# gamifyPCB.net
KiCad netlist of a schematic drawn in EAGLE
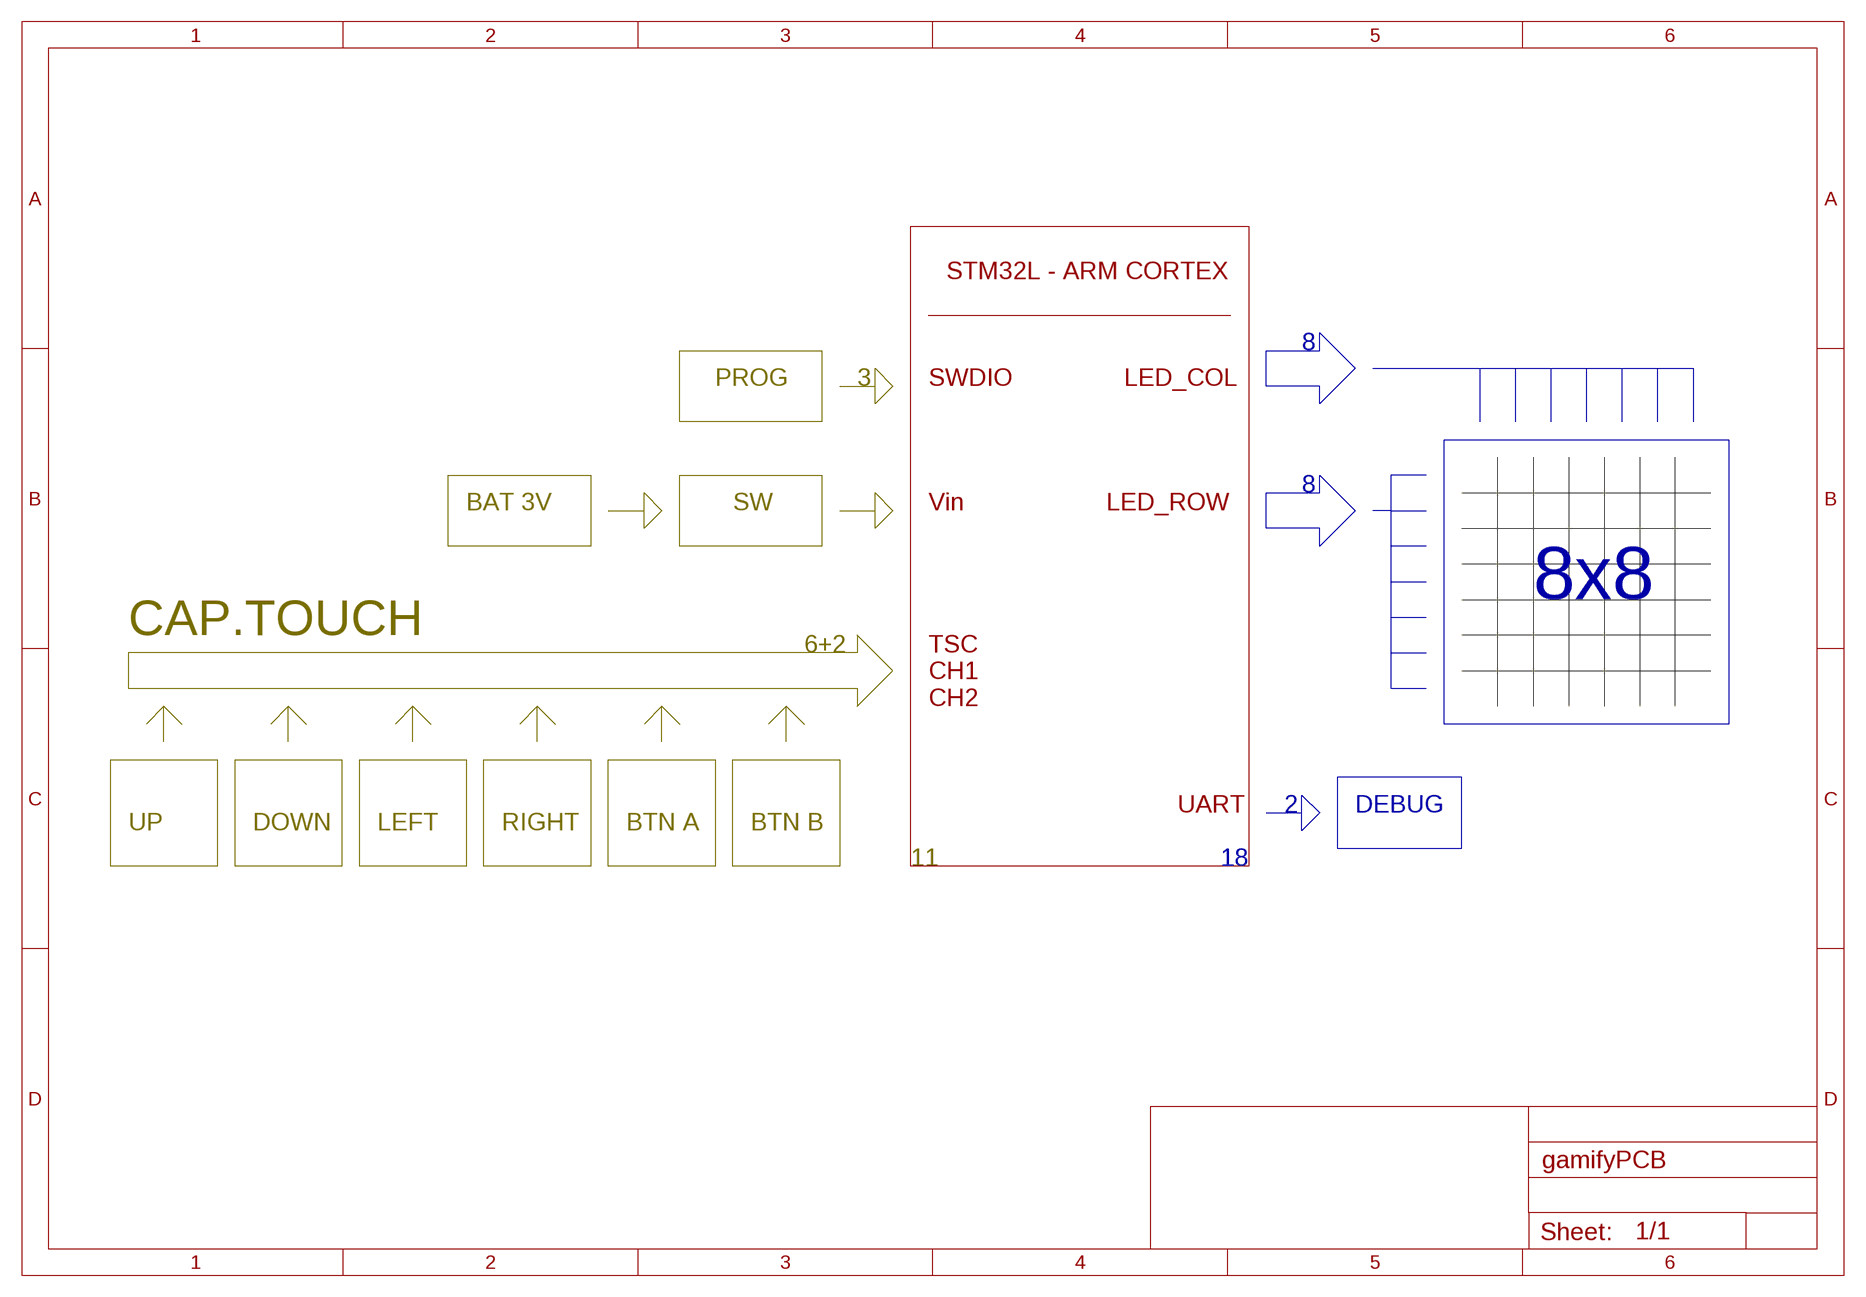
[diagram p0: schematic, sheet 1, part 1 of 2]
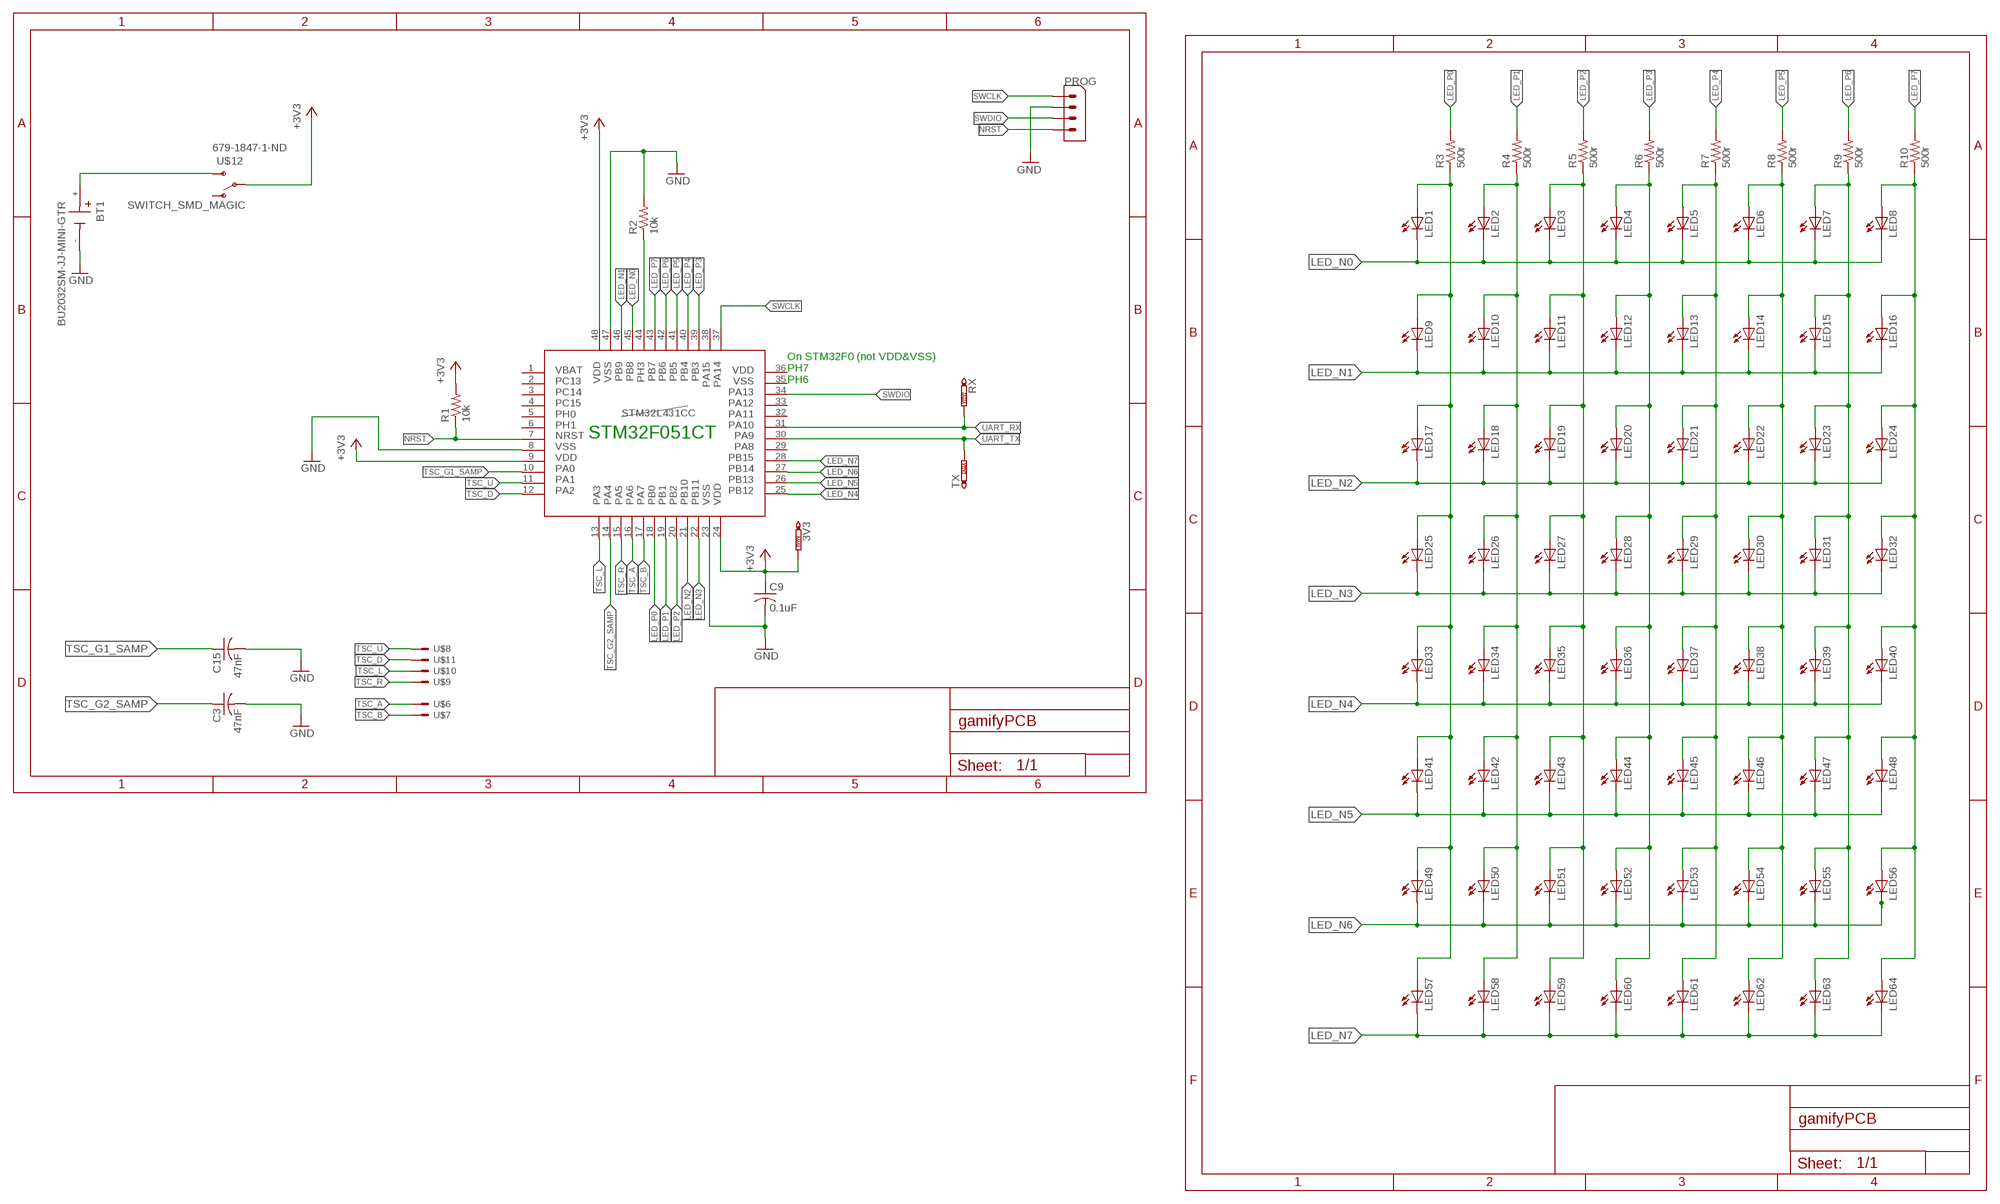
[diagram p1: schematic, sheet 1, part 2 of 2]

(export (version "E")
  (design (tool "Eeschema 10.0.6"))
  (components
    (comp (ref "3V3")
      (value "PTR1B1,27")
      (footprint "eagle-import:B1,27")
      (libsource (lib "eagle-import") (part "PTR1B1,27"))
    )
    (comp (ref "BT1")
      (value "BU2032SM-JJ-MINI-GTR")
      (footprint "eagle-import:BAT_BU2032SM-JJ-MINI-GTR")
      (fields (field (name "MF") "MPD _Memory"))
      (libsource (lib "eagle-import") (part "BU2032SM-JJ-MINI-GTR"))
    )
    (comp (ref "C3")
      (value "47nF")
      (footprint "eagle-import:C0603")
      (libsource (lib "eagle-import") (part "C-USC0603"))
    )
    (comp (ref "C9")
      (value "0.1uF")
      (footprint "eagle-import:C0603")
      (libsource (lib "eagle-import") (part "C-USC0603"))
    )
    (comp (ref "C15")
      (value "47nF")
      (footprint "eagle-import:C0603")
      (libsource (lib "eagle-import") (part "C-USC0603"))
    )
    (comp (ref "LED1")
      (value "LEDCHIP-LED0603")
      (footprint "eagle-import:CHIP-LED0603")
      (libsource (lib "eagle-import") (part "LEDCHIP-LED0603"))
    )
    (comp (ref "LED2")
      (value "LEDCHIP-LED0603")
      (footprint "eagle-import:CHIP-LED0603")
      (libsource (lib "eagle-import") (part "LEDCHIP-LED0603"))
    )
    (comp (ref "LED3")
      (value "LEDCHIP-LED0603")
      (footprint "eagle-import:CHIP-LED0603")
      (libsource (lib "eagle-import") (part "LEDCHIP-LED0603"))
    )
    (comp (ref "LED4")
      (value "LEDCHIP-LED0603")
      (footprint "eagle-import:CHIP-LED0603")
      (libsource (lib "eagle-import") (part "LEDCHIP-LED0603"))
    )
    (comp (ref "LED5")
      (value "LEDCHIP-LED0603")
      (footprint "eagle-import:CHIP-LED0603")
      (libsource (lib "eagle-import") (part "LEDCHIP-LED0603"))
    )
    (comp (ref "LED6")
      (value "LEDCHIP-LED0603")
      (footprint "eagle-import:CHIP-LED0603")
      (libsource (lib "eagle-import") (part "LEDCHIP-LED0603"))
    )
    (comp (ref "LED7")
      (value "LEDCHIP-LED0603")
      (footprint "eagle-import:CHIP-LED0603")
      (libsource (lib "eagle-import") (part "LEDCHIP-LED0603"))
    )
    (comp (ref "LED8")
      (value "LEDCHIP-LED0603")
      (footprint "eagle-import:CHIP-LED0603")
      (libsource (lib "eagle-import") (part "LEDCHIP-LED0603"))
    )
    (comp (ref "LED9")
      (value "LEDCHIP-LED0603")
      (footprint "eagle-import:CHIP-LED0603")
      (libsource (lib "eagle-import") (part "LEDCHIP-LED0603"))
    )
    (comp (ref "LED10")
      (value "LEDCHIP-LED0603")
      (footprint "eagle-import:CHIP-LED0603")
      (libsource (lib "eagle-import") (part "LEDCHIP-LED0603"))
    )
    (comp (ref "LED11")
      (value "LEDCHIP-LED0603")
      (footprint "eagle-import:CHIP-LED0603")
      (libsource (lib "eagle-import") (part "LEDCHIP-LED0603"))
    )
    (comp (ref "LED12")
      (value "LEDCHIP-LED0603")
      (footprint "eagle-import:CHIP-LED0603")
      (libsource (lib "eagle-import") (part "LEDCHIP-LED0603"))
    )
    (comp (ref "LED13")
      (value "LEDCHIP-LED0603")
      (footprint "eagle-import:CHIP-LED0603")
      (libsource (lib "eagle-import") (part "LEDCHIP-LED0603"))
    )
    (comp (ref "LED14")
      (value "LEDCHIP-LED0603")
      (footprint "eagle-import:CHIP-LED0603")
      (libsource (lib "eagle-import") (part "LEDCHIP-LED0603"))
    )
    (comp (ref "LED15")
      (value "LEDCHIP-LED0603")
      (footprint "eagle-import:CHIP-LED0603")
      (libsource (lib "eagle-import") (part "LEDCHIP-LED0603"))
    )
    (comp (ref "LED16")
      (value "LEDCHIP-LED0603")
      (footprint "eagle-import:CHIP-LED0603")
      (libsource (lib "eagle-import") (part "LEDCHIP-LED0603"))
    )
    (comp (ref "LED17")
      (value "LEDCHIP-LED0603")
      (footprint "eagle-import:CHIP-LED0603")
      (libsource (lib "eagle-import") (part "LEDCHIP-LED0603"))
    )
    (comp (ref "LED18")
      (value "LEDCHIP-LED0603")
      (footprint "eagle-import:CHIP-LED0603")
      (libsource (lib "eagle-import") (part "LEDCHIP-LED0603"))
    )
    (comp (ref "LED19")
      (value "LEDCHIP-LED0603")
      (footprint "eagle-import:CHIP-LED0603")
      (libsource (lib "eagle-import") (part "LEDCHIP-LED0603"))
    )
    (comp (ref "LED20")
      (value "LEDCHIP-LED0603")
      (footprint "eagle-import:CHIP-LED0603")
      (libsource (lib "eagle-import") (part "LEDCHIP-LED0603"))
    )
    (comp (ref "LED21")
      (value "LEDCHIP-LED0603")
      (footprint "eagle-import:CHIP-LED0603")
      (libsource (lib "eagle-import") (part "LEDCHIP-LED0603"))
    )
    (comp (ref "LED22")
      (value "LEDCHIP-LED0603")
      (footprint "eagle-import:CHIP-LED0603")
      (libsource (lib "eagle-import") (part "LEDCHIP-LED0603"))
    )
    (comp (ref "LED23")
      (value "LEDCHIP-LED0603")
      (footprint "eagle-import:CHIP-LED0603")
      (libsource (lib "eagle-import") (part "LEDCHIP-LED0603"))
    )
    (comp (ref "LED24")
      (value "LEDCHIP-LED0603")
      (footprint "eagle-import:CHIP-LED0603")
      (libsource (lib "eagle-import") (part "LEDCHIP-LED0603"))
    )
    (comp (ref "LED25")
      (value "LEDCHIP-LED0603")
      (footprint "eagle-import:CHIP-LED0603")
      (libsource (lib "eagle-import") (part "LEDCHIP-LED0603"))
    )
    (comp (ref "LED26")
      (value "LEDCHIP-LED0603")
      (footprint "eagle-import:CHIP-LED0603")
      (libsource (lib "eagle-import") (part "LEDCHIP-LED0603"))
    )
    (comp (ref "LED27")
      (value "LEDCHIP-LED0603")
      (footprint "eagle-import:CHIP-LED0603")
      (libsource (lib "eagle-import") (part "LEDCHIP-LED0603"))
    )
    (comp (ref "LED28")
      (value "LEDCHIP-LED0603")
      (footprint "eagle-import:CHIP-LED0603")
      (libsource (lib "eagle-import") (part "LEDCHIP-LED0603"))
    )
    (comp (ref "LED29")
      (value "LEDCHIP-LED0603")
      (footprint "eagle-import:CHIP-LED0603")
      (libsource (lib "eagle-import") (part "LEDCHIP-LED0603"))
    )
    (comp (ref "LED30")
      (value "LEDCHIP-LED0603")
      (footprint "eagle-import:CHIP-LED0603")
      (libsource (lib "eagle-import") (part "LEDCHIP-LED0603"))
    )
    (comp (ref "LED31")
      (value "LEDCHIP-LED0603")
      (footprint "eagle-import:CHIP-LED0603")
      (libsource (lib "eagle-import") (part "LEDCHIP-LED0603"))
    )
    (comp (ref "LED32")
      (value "LEDCHIP-LED0603")
      (footprint "eagle-import:CHIP-LED0603")
      (libsource (lib "eagle-import") (part "LEDCHIP-LED0603"))
    )
    (comp (ref "LED33")
      (value "LEDCHIP-LED0603")
      (footprint "eagle-import:CHIP-LED0603")
      (libsource (lib "eagle-import") (part "LEDCHIP-LED0603"))
    )
    (comp (ref "LED34")
      (value "LEDCHIP-LED0603")
      (footprint "eagle-import:CHIP-LED0603")
      (libsource (lib "eagle-import") (part "LEDCHIP-LED0603"))
    )
    (comp (ref "LED35")
      (value "LEDCHIP-LED0603")
      (footprint "eagle-import:CHIP-LED0603")
      (libsource (lib "eagle-import") (part "LEDCHIP-LED0603"))
    )
    (comp (ref "LED36")
      (value "LEDCHIP-LED0603")
      (footprint "eagle-import:CHIP-LED0603")
      (libsource (lib "eagle-import") (part "LEDCHIP-LED0603"))
    )
    (comp (ref "LED37")
      (value "LEDCHIP-LED0603")
      (footprint "eagle-import:CHIP-LED0603")
      (libsource (lib "eagle-import") (part "LEDCHIP-LED0603"))
    )
    (comp (ref "LED38")
      (value "LEDCHIP-LED0603")
      (footprint "eagle-import:CHIP-LED0603")
      (libsource (lib "eagle-import") (part "LEDCHIP-LED0603"))
    )
    (comp (ref "LED39")
      (value "LEDCHIP-LED0603")
      (footprint "eagle-import:CHIP-LED0603")
      (libsource (lib "eagle-import") (part "LEDCHIP-LED0603"))
    )
    (comp (ref "LED40")
      (value "LEDCHIP-LED0603")
      (footprint "eagle-import:CHIP-LED0603")
      (libsource (lib "eagle-import") (part "LEDCHIP-LED0603"))
    )
    (comp (ref "LED41")
      (value "LEDCHIP-LED0603")
      (footprint "eagle-import:CHIP-LED0603")
      (libsource (lib "eagle-import") (part "LEDCHIP-LED0603"))
    )
    (comp (ref "LED42")
      (value "LEDCHIP-LED0603")
      (footprint "eagle-import:CHIP-LED0603")
      (libsource (lib "eagle-import") (part "LEDCHIP-LED0603"))
    )
    (comp (ref "LED43")
      (value "LEDCHIP-LED0603")
      (footprint "eagle-import:CHIP-LED0603")
      (libsource (lib "eagle-import") (part "LEDCHIP-LED0603"))
    )
    (comp (ref "LED44")
      (value "LEDCHIP-LED0603")
      (footprint "eagle-import:CHIP-LED0603")
      (libsource (lib "eagle-import") (part "LEDCHIP-LED0603"))
    )
    (comp (ref "LED45")
      (value "LEDCHIP-LED0603")
      (footprint "eagle-import:CHIP-LED0603")
      (libsource (lib "eagle-import") (part "LEDCHIP-LED0603"))
    )
    (comp (ref "LED46")
      (value "LEDCHIP-LED0603")
      (footprint "eagle-import:CHIP-LED0603")
      (libsource (lib "eagle-import") (part "LEDCHIP-LED0603"))
    )
    (comp (ref "LED47")
      (value "LEDCHIP-LED0603")
      (footprint "eagle-import:CHIP-LED0603")
      (libsource (lib "eagle-import") (part "LEDCHIP-LED0603"))
    )
    (comp (ref "LED48")
      (value "LEDCHIP-LED0603")
      (footprint "eagle-import:CHIP-LED0603")
      (libsource (lib "eagle-import") (part "LEDCHIP-LED0603"))
    )
    (comp (ref "LED49")
      (value "LEDCHIP-LED0603")
      (footprint "eagle-import:CHIP-LED0603")
      (libsource (lib "eagle-import") (part "LEDCHIP-LED0603"))
    )
    (comp (ref "LED50")
      (value "LEDCHIP-LED0603")
      (footprint "eagle-import:CHIP-LED0603")
      (libsource (lib "eagle-import") (part "LEDCHIP-LED0603"))
    )
    (comp (ref "LED51")
      (value "LEDCHIP-LED0603")
      (footprint "eagle-import:CHIP-LED0603")
      (libsource (lib "eagle-import") (part "LEDCHIP-LED0603"))
    )
    (comp (ref "LED52")
      (value "LEDCHIP-LED0603")
      (footprint "eagle-import:CHIP-LED0603")
      (libsource (lib "eagle-import") (part "LEDCHIP-LED0603"))
    )
    (comp (ref "LED53")
      (value "LEDCHIP-LED0603")
      (footprint "eagle-import:CHIP-LED0603")
      (libsource (lib "eagle-import") (part "LEDCHIP-LED0603"))
    )
    (comp (ref "LED54")
      (value "LEDCHIP-LED0603")
      (footprint "eagle-import:CHIP-LED0603")
      (libsource (lib "eagle-import") (part "LEDCHIP-LED0603"))
    )
    (comp (ref "LED55")
      (value "LEDCHIP-LED0603")
      (footprint "eagle-import:CHIP-LED0603")
      (libsource (lib "eagle-import") (part "LEDCHIP-LED0603"))
    )
    (comp (ref "LED56")
      (value "LEDCHIP-LED0603")
      (footprint "eagle-import:CHIP-LED0603")
      (libsource (lib "eagle-import") (part "LEDCHIP-LED0603"))
    )
    (comp (ref "LED57")
      (value "LEDCHIP-LED0603")
      (footprint "eagle-import:CHIP-LED0603")
      (libsource (lib "eagle-import") (part "LEDCHIP-LED0603"))
    )
    (comp (ref "LED58")
      (value "LEDCHIP-LED0603")
      (footprint "eagle-import:CHIP-LED0603")
      (libsource (lib "eagle-import") (part "LEDCHIP-LED0603"))
    )
    (comp (ref "LED59")
      (value "LEDCHIP-LED0603")
      (footprint "eagle-import:CHIP-LED0603")
      (libsource (lib "eagle-import") (part "LEDCHIP-LED0603"))
    )
    (comp (ref "LED60")
      (value "LEDCHIP-LED0603")
      (footprint "eagle-import:CHIP-LED0603")
      (libsource (lib "eagle-import") (part "LEDCHIP-LED0603"))
    )
    (comp (ref "LED61")
      (value "LEDCHIP-LED0603")
      (footprint "eagle-import:CHIP-LED0603")
      (libsource (lib "eagle-import") (part "LEDCHIP-LED0603"))
    )
    (comp (ref "LED62")
      (value "LEDCHIP-LED0603")
      (footprint "eagle-import:CHIP-LED0603")
      (libsource (lib "eagle-import") (part "LEDCHIP-LED0603"))
    )
    (comp (ref "LED63")
      (value "LEDCHIP-LED0603")
      (footprint "eagle-import:CHIP-LED0603")
      (libsource (lib "eagle-import") (part "LEDCHIP-LED0603"))
    )
    (comp (ref "LED64")
      (value "LEDCHIP-LED0603")
      (footprint "eagle-import:CHIP-LED0603")
      (libsource (lib "eagle-import") (part "LEDCHIP-LED0603"))
    )
    (comp (ref "PROG")
      (value "4-PIN-1.25MM")
      (footprint "eagle-import:4-PIN-1.25MM")
      (libsource (lib "eagle-import") (part "4-PIN-1.25MM"))
    )
    (comp (ref "R1")
      (value "10k")
      (footprint "eagle-import:R0603")
      (libsource (lib "eagle-import") (part "R-US_R0603"))
    )
    (comp (ref "R2")
      (value "10k")
      (footprint "eagle-import:R0603")
      (libsource (lib "eagle-import") (part "R-US_R0603"))
    )
    (comp (ref "R3")
      (value "500r")
      (footprint "eagle-import:R0603")
      (libsource (lib "eagle-import") (part "R-US_R0603"))
    )
    (comp (ref "R4")
      (value "500r")
      (footprint "eagle-import:R0603")
      (libsource (lib "eagle-import") (part "R-US_R0603"))
    )
    (comp (ref "R5")
      (value "500r")
      (footprint "eagle-import:R0603")
      (libsource (lib "eagle-import") (part "R-US_R0603"))
    )
    (comp (ref "R6")
      (value "500r")
      (footprint "eagle-import:R0603")
      (libsource (lib "eagle-import") (part "R-US_R0603"))
    )
    (comp (ref "R7")
      (value "500r")
      (footprint "eagle-import:R0603")
      (libsource (lib "eagle-import") (part "R-US_R0603"))
    )
    (comp (ref "R8")
      (value "500r")
      (footprint "eagle-import:R0603")
      (libsource (lib "eagle-import") (part "R-US_R0603"))
    )
    (comp (ref "R9")
      (value "500r")
      (footprint "eagle-import:R0603")
      (libsource (lib "eagle-import") (part "R-US_R0603"))
    )
    (comp (ref "R10")
      (value "500r")
      (footprint "eagle-import:R0603")
      (libsource (lib "eagle-import") (part "R-US_R0603"))
    )
    (comp (ref "RX")
      (value "PTR1B1,27")
      (footprint "eagle-import:B1,27")
      (libsource (lib "eagle-import") (part "PTR1B1,27"))
    )
    (comp (ref "TX")
      (value "PTR1B1,27")
      (footprint "eagle-import:B1,27")
      (libsource (lib "eagle-import") (part "PTR1B1,27"))
    )
    (comp (ref "U$2")
      (value "STM32L431CC")
      (footprint "eagle-import:QFP50P900X900X160-48")
      (libsource (lib "eagle-import") (part "STM32L431CC"))
    )
    (comp (ref "U$6")
      (value "CAP_BUTTON")
      (footprint "eagle-import:CAPBUTTON")
      (libsource (lib "eagle-import") (part "CAP_BUTTON"))
    )
    (comp (ref "U$7")
      (value "CAP_BUTTON")
      (footprint "eagle-import:CAPBUTTON")
      (libsource (lib "eagle-import") (part "CAP_BUTTON"))
    )
    (comp (ref "U$8")
      (value "CAP_DPAD")
      (footprint "eagle-import:DPAD")
      (libsource (lib "eagle-import") (part "CAP_DPAD"))
    )
    (comp (ref "U$9")
      (value "CAP_DPAD")
      (footprint "eagle-import:DPAD")
      (libsource (lib "eagle-import") (part "CAP_DPAD"))
    )
    (comp (ref "U$10")
      (value "CAP_DPAD")
      (footprint "eagle-import:DPAD")
      (libsource (lib "eagle-import") (part "CAP_DPAD"))
    )
    (comp (ref "U$11")
      (value "CAP_DPAD")
      (footprint "eagle-import:DPAD")
      (libsource (lib "eagle-import") (part "CAP_DPAD"))
    )
    (comp (ref "U$12")
      (value "SWITCH_SMD_MAGIC")
      (footprint "eagle-import:SWITCH_SMD_SUNKEN")
      (libsource (lib "eagle-import") (part "SWITCH_SMD_MAGIC"))
    )
  )
  (nets
    (net (code "1") (name "+3V3") (class "Default")
      (node (ref "3V3") (pin "TP") (pinfunction "TP_TP") (pintype "input"))
      (node (ref "C9") (pin "1") (pinfunction "1_1") (pintype "passive"))
      (node (ref "R1") (pin "2") (pinfunction "2_2") (pintype "passive"))
      (node (ref "U$12") (pin "2") (pinfunction "P_2") (pintype "passive"))
      (node (ref "U$2") (pin "24") (pinfunction "P$24_24") (pintype "bidirectional"))
      (node (ref "U$2") (pin "48") (pinfunction "P$48_48") (pintype "bidirectional"))
      (node (ref "U$2") (pin "9") (pinfunction "P$9_9") (pintype "bidirectional"))
    )
    (net (code "2") (name "GND") (class "Default")
      (node (ref "BT1") (pin "-") (pinfunction "-_-") (pintype "passive"))
      (node (ref "C15") (pin "2") (pinfunction "2_2") (pintype "passive"))
      (node (ref "C3") (pin "2") (pinfunction "2_2") (pintype "passive"))
      (node (ref "C9") (pin "2") (pinfunction "2_2") (pintype "passive"))
      (node (ref "PROG") (pin "P$3") (pinfunction "2_P$3") (pintype "bidirectional"))
      (node (ref "R2") (pin "2") (pinfunction "2_2") (pintype "passive"))
      (node (ref "U$2") (pin "23") (pinfunction "P$23_23") (pintype "bidirectional"))
      (node (ref "U$2") (pin "47") (pinfunction "P$47_47") (pintype "bidirectional"))
      (node (ref "U$2") (pin "8") (pinfunction "P$8_8") (pintype "bidirectional"))
    )
    (net (code "3") (name "LED_N0") (class "Default")
      (node (ref "LED1") (pin "C") (pinfunction "C_C") (pintype "passive"))
      (node (ref "LED2") (pin "C") (pinfunction "C_C") (pintype "passive"))
      (node (ref "LED3") (pin "C") (pinfunction "C_C") (pintype "passive"))
      (node (ref "LED4") (pin "C") (pinfunction "C_C") (pintype "passive"))
      (node (ref "LED5") (pin "C") (pinfunction "C_C") (pintype "passive"))
      (node (ref "LED6") (pin "C") (pinfunction "C_C") (pintype "passive"))
      (node (ref "LED7") (pin "C") (pinfunction "C_C") (pintype "passive"))
      (node (ref "LED8") (pin "C") (pinfunction "C_C") (pintype "passive"))
      (node (ref "U$2") (pin "45") (pinfunction "P$45_45") (pintype "bidirectional"))
    )
    (net (code "4") (name "LED_N1") (class "Default")
      (node (ref "LED10") (pin "C") (pinfunction "C_C") (pintype "passive"))
      (node (ref "LED11") (pin "C") (pinfunction "C_C") (pintype "passive"))
      (node (ref "LED12") (pin "C") (pinfunction "C_C") (pintype "passive"))
      (node (ref "LED13") (pin "C") (pinfunction "C_C") (pintype "passive"))
      (node (ref "LED14") (pin "C") (pinfunction "C_C") (pintype "passive"))
      (node (ref "LED15") (pin "C") (pinfunction "C_C") (pintype "passive"))
      (node (ref "LED16") (pin "C") (pinfunction "C_C") (pintype "passive"))
      (node (ref "LED9") (pin "C") (pinfunction "C_C") (pintype "passive"))
      (node (ref "U$2") (pin "46") (pinfunction "P$46_46") (pintype "bidirectional"))
    )
    (net (code "5") (name "LED_N2") (class "Default")
      (node (ref "LED17") (pin "C") (pinfunction "C_C") (pintype "passive"))
      (node (ref "LED18") (pin "C") (pinfunction "C_C") (pintype "passive"))
      (node (ref "LED19") (pin "C") (pinfunction "C_C") (pintype "passive"))
      (node (ref "LED20") (pin "C") (pinfunction "C_C") (pintype "passive"))
      (node (ref "LED21") (pin "C") (pinfunction "C_C") (pintype "passive"))
      (node (ref "LED22") (pin "C") (pinfunction "C_C") (pintype "passive"))
      (node (ref "LED23") (pin "C") (pinfunction "C_C") (pintype "passive"))
      (node (ref "LED24") (pin "C") (pinfunction "C_C") (pintype "passive"))
      (node (ref "U$2") (pin "21") (pinfunction "P$21_21") (pintype "bidirectional"))
    )
    (net (code "6") (name "LED_N3") (class "Default")
      (node (ref "LED25") (pin "C") (pinfunction "C_C") (pintype "passive"))
      (node (ref "LED26") (pin "C") (pinfunction "C_C") (pintype "passive"))
      (node (ref "LED27") (pin "C") (pinfunction "C_C") (pintype "passive"))
      (node (ref "LED28") (pin "C") (pinfunction "C_C") (pintype "passive"))
      (node (ref "LED29") (pin "C") (pinfunction "C_C") (pintype "passive"))
      (node (ref "LED30") (pin "C") (pinfunction "C_C") (pintype "passive"))
      (node (ref "LED31") (pin "C") (pinfunction "C_C") (pintype "passive"))
      (node (ref "LED32") (pin "C") (pinfunction "C_C") (pintype "passive"))
      (node (ref "U$2") (pin "22") (pinfunction "P$22_22") (pintype "bidirectional"))
    )
    (net (code "7") (name "LED_N4") (class "Default")
      (node (ref "LED33") (pin "C") (pinfunction "C_C") (pintype "passive"))
      (node (ref "LED34") (pin "C") (pinfunction "C_C") (pintype "passive"))
      (node (ref "LED35") (pin "C") (pinfunction "C_C") (pintype "passive"))
      (node (ref "LED36") (pin "C") (pinfunction "C_C") (pintype "passive"))
      (node (ref "LED37") (pin "C") (pinfunction "C_C") (pintype "passive"))
      (node (ref "LED38") (pin "C") (pinfunction "C_C") (pintype "passive"))
      (node (ref "LED39") (pin "C") (pinfunction "C_C") (pintype "passive"))
      (node (ref "LED40") (pin "C") (pinfunction "C_C") (pintype "passive"))
      (node (ref "U$2") (pin "25") (pinfunction "P$25_25") (pintype "bidirectional"))
    )
    (net (code "8") (name "LED_N5") (class "Default")
      (node (ref "LED41") (pin "C") (pinfunction "C_C") (pintype "passive"))
      (node (ref "LED42") (pin "C") (pinfunction "C_C") (pintype "passive"))
      (node (ref "LED43") (pin "C") (pinfunction "C_C") (pintype "passive"))
      (node (ref "LED44") (pin "C") (pinfunction "C_C") (pintype "passive"))
      (node (ref "LED45") (pin "C") (pinfunction "C_C") (pintype "passive"))
      (node (ref "LED46") (pin "C") (pinfunction "C_C") (pintype "passive"))
      (node (ref "LED47") (pin "C") (pinfunction "C_C") (pintype "passive"))
      (node (ref "LED48") (pin "C") (pinfunction "C_C") (pintype "passive"))
      (node (ref "U$2") (pin "26") (pinfunction "P$26_26") (pintype "bidirectional"))
    )
    (net (code "9") (name "LED_N6") (class "Default")
      (node (ref "LED49") (pin "C") (pinfunction "C_C") (pintype "passive"))
      (node (ref "LED50") (pin "C") (pinfunction "C_C") (pintype "passive"))
      (node (ref "LED51") (pin "C") (pinfunction "C_C") (pintype "passive"))
      (node (ref "LED52") (pin "C") (pinfunction "C_C") (pintype "passive"))
      (node (ref "LED53") (pin "C") (pinfunction "C_C") (pintype "passive"))
      (node (ref "LED54") (pin "C") (pinfunction "C_C") (pintype "passive"))
      (node (ref "LED55") (pin "C") (pinfunction "C_C") (pintype "passive"))
      (node (ref "LED56") (pin "C") (pinfunction "C_C") (pintype "passive"))
      (node (ref "U$2") (pin "27") (pinfunction "P$27_27") (pintype "bidirectional"))
    )
    (net (code "10") (name "LED_N7") (class "Default")
      (node (ref "LED57") (pin "C") (pinfunction "C_C") (pintype "passive"))
      (node (ref "LED58") (pin "C") (pinfunction "C_C") (pintype "passive"))
      (node (ref "LED59") (pin "C") (pinfunction "C_C") (pintype "passive"))
      (node (ref "LED60") (pin "C") (pinfunction "C_C") (pintype "passive"))
      (node (ref "LED61") (pin "C") (pinfunction "C_C") (pintype "passive"))
      (node (ref "LED62") (pin "C") (pinfunction "C_C") (pintype "passive"))
      (node (ref "LED63") (pin "C") (pinfunction "C_C") (pintype "passive"))
      (node (ref "LED64") (pin "C") (pinfunction "C_C") (pintype "passive"))
      (node (ref "U$2") (pin "28") (pinfunction "P$28_28") (pintype "bidirectional"))
    )
    (net (code "11") (name "LED_P0") (class "Default")
      (node (ref "R3") (pin "2") (pinfunction "2_2") (pintype "passive"))
      (node (ref "U$2") (pin "18") (pinfunction "P$18_18") (pintype "bidirectional"))
    )
    (net (code "12") (name "LED_P1") (class "Default")
      (node (ref "R4") (pin "2") (pinfunction "2_2") (pintype "passive"))
      (node (ref "U$2") (pin "19") (pinfunction "P$19_19") (pintype "bidirectional"))
    )
    (net (code "13") (name "LED_P2") (class "Default")
      (node (ref "R5") (pin "2") (pinfunction "2_2") (pintype "passive"))
      (node (ref "U$2") (pin "20") (pinfunction "P$20_20") (pintype "bidirectional"))
    )
    (net (code "14") (name "LED_P3") (class "Default")
      (node (ref "R6") (pin "2") (pinfunction "2_2") (pintype "passive"))
      (node (ref "U$2") (pin "39") (pinfunction "P$39_39") (pintype "bidirectional"))
    )
    (net (code "15") (name "LED_P4") (class "Default")
      (node (ref "R7") (pin "2") (pinfunction "2_2") (pintype "passive"))
      (node (ref "U$2") (pin "40") (pinfunction "P$40_40") (pintype "bidirectional"))
    )
    (net (code "16") (name "LED_P5") (class "Default")
      (node (ref "R8") (pin "2") (pinfunction "2_2") (pintype "passive"))
      (node (ref "U$2") (pin "41") (pinfunction "P$41_41") (pintype "bidirectional"))
    )
    (net (code "17") (name "LED_P6") (class "Default")
      (node (ref "R9") (pin "2") (pinfunction "2_2") (pintype "passive"))
      (node (ref "U$2") (pin "42") (pinfunction "P$42_42") (pintype "bidirectional"))
    )
    (net (code "18") (name "LED_P7") (class "Default")
      (node (ref "R10") (pin "2") (pinfunction "2_2") (pintype "passive"))
      (node (ref "U$2") (pin "43") (pinfunction "P$43_43") (pintype "bidirectional"))
    )
    (net (code "19") (name "NRST") (class "Default")
      (node (ref "PROG") (pin "P$1") (pinfunction "4_P$1") (pintype "bidirectional"))
      (node (ref "R1") (pin "1") (pinfunction "1_1") (pintype "passive"))
      (node (ref "U$2") (pin "7") (pinfunction "P$7_7") (pintype "bidirectional"))
    )
    (net (code "20") (name "Net-(LED1-PadA)") (class "Default")
      (node (ref "LED1") (pin "A") (pinfunction "A_A") (pintype "passive"))
      (node (ref "LED17") (pin "A") (pinfunction "A_A") (pintype "passive"))
      (node (ref "LED25") (pin "A") (pinfunction "A_A") (pintype "passive"))
      (node (ref "LED33") (pin "A") (pinfunction "A_A") (pintype "passive"))
      (node (ref "LED41") (pin "A") (pinfunction "A_A") (pintype "passive"))
      (node (ref "LED49") (pin "A") (pinfunction "A_A") (pintype "passive"))
      (node (ref "LED57") (pin "A") (pinfunction "A_A") (pintype "passive"))
      (node (ref "LED9") (pin "A") (pinfunction "A_A") (pintype "passive"))
      (node (ref "R3") (pin "1") (pinfunction "1_1") (pintype "passive"))
    )
    (net (code "21") (name "Net-(LED10-PadA)") (class "Default")
      (node (ref "LED10") (pin "A") (pinfunction "A_A") (pintype "passive"))
      (node (ref "LED18") (pin "A") (pinfunction "A_A") (pintype "passive"))
      (node (ref "LED2") (pin "A") (pinfunction "A_A") (pintype "passive"))
      (node (ref "LED26") (pin "A") (pinfunction "A_A") (pintype "passive"))
      (node (ref "LED34") (pin "A") (pinfunction "A_A") (pintype "passive"))
      (node (ref "LED42") (pin "A") (pinfunction "A_A") (pintype "passive"))
      (node (ref "LED50") (pin "A") (pinfunction "A_A") (pintype "passive"))
      (node (ref "LED58") (pin "A") (pinfunction "A_A") (pintype "passive"))
      (node (ref "R4") (pin "1") (pinfunction "1_1") (pintype "passive"))
    )
    (net (code "22") (name "Net-(LED11-PadA)") (class "Default")
      (node (ref "LED11") (pin "A") (pinfunction "A_A") (pintype "passive"))
      (node (ref "LED19") (pin "A") (pinfunction "A_A") (pintype "passive"))
      (node (ref "LED27") (pin "A") (pinfunction "A_A") (pintype "passive"))
      (node (ref "LED3") (pin "A") (pinfunction "A_A") (pintype "passive"))
      (node (ref "LED35") (pin "A") (pinfunction "A_A") (pintype "passive"))
      (node (ref "LED43") (pin "A") (pinfunction "A_A") (pintype "passive"))
      (node (ref "LED51") (pin "A") (pinfunction "A_A") (pintype "passive"))
      (node (ref "LED59") (pin "A") (pinfunction "A_A") (pintype "passive"))
      (node (ref "R5") (pin "1") (pinfunction "1_1") (pintype "passive"))
    )
    (net (code "23") (name "Net-(LED12-PadA)") (class "Default")
      (node (ref "LED12") (pin "A") (pinfunction "A_A") (pintype "passive"))
      (node (ref "LED20") (pin "A") (pinfunction "A_A") (pintype "passive"))
      (node (ref "LED28") (pin "A") (pinfunction "A_A") (pintype "passive"))
      (node (ref "LED36") (pin "A") (pinfunction "A_A") (pintype "passive"))
      (node (ref "LED4") (pin "A") (pinfunction "A_A") (pintype "passive"))
      (node (ref "LED44") (pin "A") (pinfunction "A_A") (pintype "passive"))
      (node (ref "LED52") (pin "A") (pinfunction "A_A") (pintype "passive"))
      (node (ref "LED60") (pin "A") (pinfunction "A_A") (pintype "passive"))
      (node (ref "R6") (pin "1") (pinfunction "1_1") (pintype "passive"))
    )
    (net (code "24") (name "Net-(LED13-PadA)") (class "Default")
      (node (ref "LED13") (pin "A") (pinfunction "A_A") (pintype "passive"))
      (node (ref "LED21") (pin "A") (pinfunction "A_A") (pintype "passive"))
      (node (ref "LED29") (pin "A") (pinfunction "A_A") (pintype "passive"))
      (node (ref "LED37") (pin "A") (pinfunction "A_A") (pintype "passive"))
      (node (ref "LED45") (pin "A") (pinfunction "A_A") (pintype "passive"))
      (node (ref "LED5") (pin "A") (pinfunction "A_A") (pintype "passive"))
      (node (ref "LED53") (pin "A") (pinfunction "A_A") (pintype "passive"))
      (node (ref "LED61") (pin "A") (pinfunction "A_A") (pintype "passive"))
      (node (ref "R7") (pin "1") (pinfunction "1_1") (pintype "passive"))
    )
    (net (code "25") (name "Net-(LED14-PadA)") (class "Default")
      (node (ref "LED14") (pin "A") (pinfunction "A_A") (pintype "passive"))
      (node (ref "LED22") (pin "A") (pinfunction "A_A") (pintype "passive"))
      (node (ref "LED30") (pin "A") (pinfunction "A_A") (pintype "passive"))
      (node (ref "LED38") (pin "A") (pinfunction "A_A") (pintype "passive"))
      (node (ref "LED46") (pin "A") (pinfunction "A_A") (pintype "passive"))
      (node (ref "LED54") (pin "A") (pinfunction "A_A") (pintype "passive"))
      (node (ref "LED6") (pin "A") (pinfunction "A_A") (pintype "passive"))
      (node (ref "LED62") (pin "A") (pinfunction "A_A") (pintype "passive"))
      (node (ref "R8") (pin "1") (pinfunction "1_1") (pintype "passive"))
    )
    (net (code "26") (name "Net-(LED15-PadA)") (class "Default")
      (node (ref "LED15") (pin "A") (pinfunction "A_A") (pintype "passive"))
      (node (ref "LED23") (pin "A") (pinfunction "A_A") (pintype "passive"))
      (node (ref "LED31") (pin "A") (pinfunction "A_A") (pintype "passive"))
      (node (ref "LED39") (pin "A") (pinfunction "A_A") (pintype "passive"))
      (node (ref "LED47") (pin "A") (pinfunction "A_A") (pintype "passive"))
      (node (ref "LED55") (pin "A") (pinfunction "A_A") (pintype "passive"))
      (node (ref "LED63") (pin "A") (pinfunction "A_A") (pintype "passive"))
      (node (ref "LED7") (pin "A") (pinfunction "A_A") (pintype "passive"))
      (node (ref "R9") (pin "1") (pinfunction "1_1") (pintype "passive"))
    )
    (net (code "27") (name "Net-(LED16-PadA)") (class "Default")
      (node (ref "LED16") (pin "A") (pinfunction "A_A") (pintype "passive"))
      (node (ref "LED24") (pin "A") (pinfunction "A_A") (pintype "passive"))
      (node (ref "LED32") (pin "A") (pinfunction "A_A") (pintype "passive"))
      (node (ref "LED40") (pin "A") (pinfunction "A_A") (pintype "passive"))
      (node (ref "LED48") (pin "A") (pinfunction "A_A") (pintype "passive"))
      (node (ref "LED56") (pin "A") (pinfunction "A_A") (pintype "passive"))
      (node (ref "LED64") (pin "A") (pinfunction "A_A") (pintype "passive"))
      (node (ref "LED8") (pin "A") (pinfunction "A_A") (pintype "passive"))
      (node (ref "R10") (pin "1") (pinfunction "1_1") (pintype "passive"))
    )
    (net (code "28") (name "Net-(U$2-P$44)") (class "Default")
      (node (ref "R2") (pin "1") (pinfunction "1_1") (pintype "passive"))
      (node (ref "U$2") (pin "44") (pinfunction "P$44_44") (pintype "bidirectional"))
    )
    (net (code "29") (name "Net-(U$12-S)") (class "Default")
      (node (ref "BT1") (pin "+") (pinfunction "+_+") (pintype "passive"))
      (node (ref "U$12") (pin "3") (pinfunction "S_3") (pintype "passive"))
    )
    (net (code "30") (name "SWCLK") (class "Default")
      (node (ref "PROG") (pin "P$4") (pinfunction "1_P$4") (pintype "bidirectional"))
      (node (ref "U$2") (pin "37") (pinfunction "P$37_37") (pintype "bidirectional"))
    )
    (net (code "31") (name "SWDIO") (class "Default")
      (node (ref "PROG") (pin "P$2") (pinfunction "3_P$2") (pintype "bidirectional"))
      (node (ref "U$2") (pin "34") (pinfunction "P$34_34") (pintype "bidirectional"))
    )
    (net (code "32") (name "TSC_A") (class "Default")
      (node (ref "U$2") (pin "16") (pinfunction "P$16_16") (pintype "bidirectional"))
      (node (ref "U$6") (pin "P$1") (pinfunction "S_P$1") (pintype "passive"))
      (node (ref "U$6") (pin "P$2") (pinfunction "S_P$2") (pintype "passive"))
    )
    (net (code "33") (name "TSC_B") (class "Default")
      (node (ref "U$2") (pin "17") (pinfunction "P$17_17") (pintype "bidirectional"))
      (node (ref "U$7") (pin "P$1") (pinfunction "S_P$1") (pintype "passive"))
      (node (ref "U$7") (pin "P$2") (pinfunction "S_P$2") (pintype "passive"))
    )
    (net (code "34") (name "TSC_D") (class "Default")
      (node (ref "U$11") (pin "P$1") (pinfunction "S_P$1") (pintype "passive"))
      (node (ref "U$2") (pin "12") (pinfunction "P$12_12") (pintype "bidirectional"))
    )
    (net (code "35") (name "TSC_G1_SAMP") (class "Default")
      (node (ref "C15") (pin "1") (pinfunction "1_1") (pintype "passive"))
      (node (ref "U$2") (pin "10") (pinfunction "P$10_10") (pintype "bidirectional"))
    )
    (net (code "36") (name "TSC_G2_SAMP") (class "Default")
      (node (ref "C3") (pin "1") (pinfunction "1_1") (pintype "passive"))
      (node (ref "U$2") (pin "14") (pinfunction "P$14_14") (pintype "bidirectional"))
    )
    (net (code "37") (name "TSC_L") (class "Default")
      (node (ref "U$10") (pin "P$1") (pinfunction "S_P$1") (pintype "passive"))
      (node (ref "U$2") (pin "13") (pinfunction "P$13_13") (pintype "bidirectional"))
    )
    (net (code "38") (name "TSC_R") (class "Default")
      (node (ref "U$2") (pin "15") (pinfunction "P$15_15") (pintype "bidirectional"))
      (node (ref "U$9") (pin "P$1") (pinfunction "S_P$1") (pintype "passive"))
    )
    (net (code "39") (name "TSC_U") (class "Default")
      (node (ref "U$2") (pin "11") (pinfunction "P$11_11") (pintype "bidirectional"))
      (node (ref "U$8") (pin "P$1") (pinfunction "S_P$1") (pintype "passive"))
    )
    (net (code "40") (name "UART_RX") (class "Default")
      (node (ref "RX") (pin "TP") (pinfunction "TP_TP") (pintype "input"))
      (node (ref "U$2") (pin "31") (pinfunction "P$31_31") (pintype "bidirectional"))
    )
    (net (code "41") (name "UART_TX") (class "Default")
      (node (ref "TX") (pin "TP") (pinfunction "TP_TP") (pintype "input"))
      (node (ref "U$2") (pin "30") (pinfunction "P$30_30") (pintype "bidirectional"))
    )
    (net (code "42") (name "unconnected-(U$2-P$1-Pad1)") (class "Default")
      (node (ref "U$2") (pin "1") (pinfunction "P$1_1") (pintype "bidirectional"))
    )
    (net (code "43") (name "unconnected-(U$2-P$2-Pad2)") (class "Default")
      (node (ref "U$2") (pin "2") (pinfunction "P$2_2") (pintype "bidirectional"))
    )
    (net (code "44") (name "unconnected-(U$2-P$3-Pad3)") (class "Default")
      (node (ref "U$2") (pin "3") (pinfunction "P$3_3") (pintype "bidirectional"))
    )
    (net (code "45") (name "unconnected-(U$2-P$4-Pad4)") (class "Default")
      (node (ref "U$2") (pin "4") (pinfunction "P$4_4") (pintype "bidirectional"))
    )
    (net (code "46") (name "unconnected-(U$2-P$5-Pad5)") (class "Default")
      (node (ref "U$2") (pin "5") (pinfunction "P$5_5") (pintype "bidirectional"))
    )
    (net (code "47") (name "unconnected-(U$2-P$6-Pad6)") (class "Default")
      (node (ref "U$2") (pin "6") (pinfunction "P$6_6") (pintype "bidirectional"))
    )
    (net (code "48") (name "unconnected-(U$2-P$29-Pad29)") (class "Default")
      (node (ref "U$2") (pin "29") (pinfunction "P$29_29") (pintype "bidirectional"))
    )
    (net (code "49") (name "unconnected-(U$2-P$32-Pad32)") (class "Default")
      (node (ref "U$2") (pin "32") (pinfunction "P$32_32") (pintype "bidirectional"))
    )
    (net (code "50") (name "unconnected-(U$2-P$33-Pad33)") (class "Default")
      (node (ref "U$2") (pin "33") (pinfunction "P$33_33") (pintype "bidirectional"))
    )
    (net (code "51") (name "unconnected-(U$2-P$35-Pad35)") (class "Default")
      (node (ref "U$2") (pin "35") (pinfunction "P$35_35") (pintype "bidirectional"))
    )
    (net (code "52") (name "unconnected-(U$2-P$36-Pad36)") (class "Default")
      (node (ref "U$2") (pin "36") (pinfunction "P$36_36") (pintype "bidirectional"))
    )
    (net (code "53") (name "unconnected-(U$2-P$38-Pad38)") (class "Default")
      (node (ref "U$2") (pin "38") (pinfunction "P$38_38") (pintype "bidirectional"))
    )
    (net (code "54") (name "unconnected-(U$12-O-Pad1)") (class "Default")
      (node (ref "U$12") (pin "1") (pinfunction "O_1") (pintype "passive"))
    )
  )
)
